# HM_SHT21.net
KiCad netlist of a schematic drawn in EAGLE
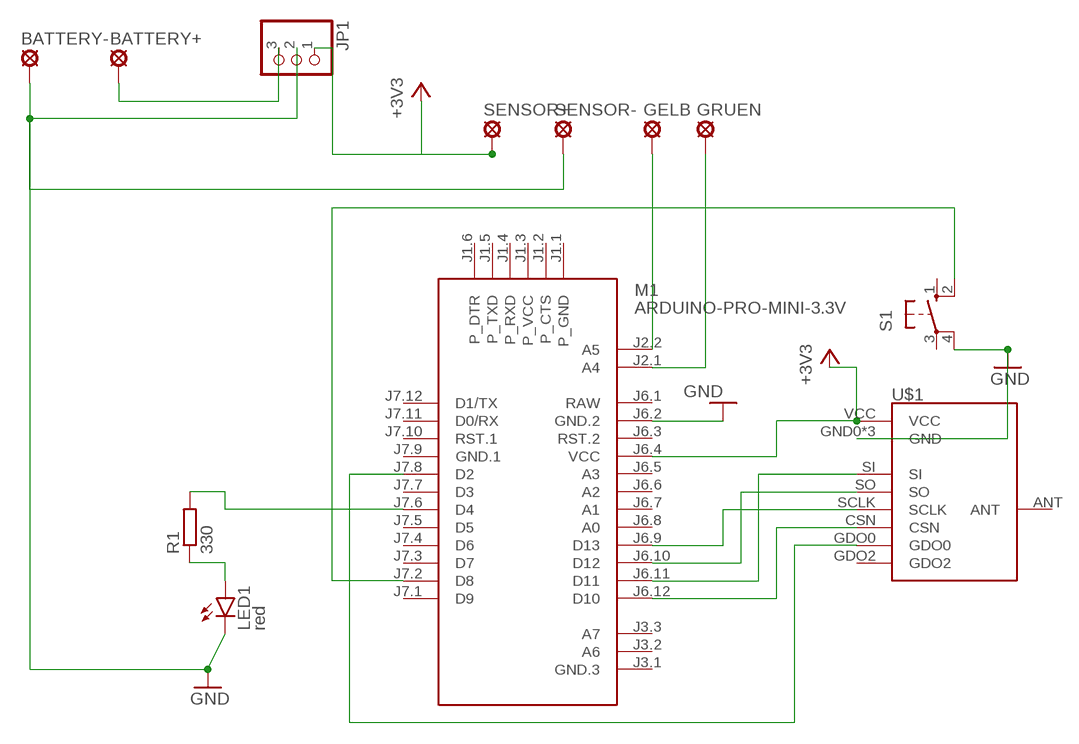
[diagram p0: schematic, sheet 1]

(export (version "E")
  (design (tool "Eeschema 10.0.6"))
  (components
    (comp (ref "BATTERY+")
      (value "LSP11")
      (footprint "eagle-import:LSP11")
      (libsource (lib "eagle-import") (part "LSP11"))
    )
    (comp (ref "BATTERY-")
      (value "LSP11")
      (footprint "eagle-import:LSP11")
      (libsource (lib "eagle-import") (part "LSP11"))
    )
    (comp (ref "GELB")
      (value "LSP11")
      (footprint "eagle-import:LSP11")
      (libsource (lib "eagle-import") (part "LSP11"))
    )
    (comp (ref "GRUEN")
      (value "LSP11")
      (footprint "eagle-import:LSP11")
      (libsource (lib "eagle-import") (part "LSP11"))
    )
    (comp (ref "JP1")
      (value "PINHD-1X3")
      (footprint "eagle-import:1X03")
      (libsource (lib "eagle-import") (part "PINHD-1X3"))
    )
    (comp (ref "LED1")
      (value "red")
      (footprint "eagle-import:LED5MM")
      (libsource (lib "eagle-import") (part "LED5MM"))
    )
    (comp (ref "M1")
      (value "ARDUINO-PRO-MINI-3.3V")
      (footprint "eagle-import:ARDUINO-PRO-MINI")
      (libsource (lib "eagle-import") (part "ARDUINO-PRO-MINI-3.3V"))
    )
    (comp (ref "R1")
      (value "330")
      (footprint "eagle-import:0204_7")
      (libsource (lib "eagle-import") (part "R-EU_0204/7"))
    )
    (comp (ref "S1")
      (value "10-XX")
      (footprint "eagle-import:B3F-10XX")
      (fields (field (name "MPN") "B3F-1000"))
      (libsource (lib "eagle-import") (part "10-XX"))
    )
    (comp (ref "SENSOR+")
      (value "LSP11")
      (footprint "eagle-import:LSP11")
      (libsource (lib "eagle-import") (part "LSP11"))
    )
    (comp (ref "SENSOR-")
      (value "LSP11")
      (footprint "eagle-import:LSP11")
      (libsource (lib "eagle-import") (part "LSP11"))
    )
    (comp (ref "U$1")
      (value "CC1101")
      (footprint "eagle-import:CC1101")
      (libsource (lib "eagle-import") (part "CC1101"))
    )
  )
  (nets
    (net (code "1") (name "+3V3") (class "Default")
      (node (ref "JP1") (pin "1") (pinfunction "1_1") (pintype "passive"))
      (node (ref "M1") (pin "J6.4") (pinfunction "VCC_J6.4") (pintype "power_in"))
      (node (ref "SENSOR+") (pin "MP") (pinfunction "MP_MP") (pintype "passive"))
      (node (ref "U$1") (pin "VCC") (pinfunction "VCC_VCC") (pintype "power_in"))
    )
    (net (code "2") (name "/GND.1") (class "Default")
      (node (ref "M1") (pin "J7.9") (pinfunction "GND.1_J7.9") (pintype "power_in"))
    )
    (net (code "3") (name "/RAW") (class "Default")
      (node (ref "M1") (pin "J6.1") (pinfunction "RAW_J6.1") (pintype "power_in"))
    )
    (net (code "4") (name "GND") (class "Default")
      (node (ref "BATTERY-") (pin "MP") (pinfunction "MP_MP") (pintype "passive"))
      (node (ref "JP1") (pin "2") (pinfunction "2_2") (pintype "passive"))
      (node (ref "LED1") (pin "K") (pinfunction "C_K") (pintype "passive"))
      (node (ref "M1") (pin "J6.2") (pinfunction "GND.2_J6.2") (pintype "power_in"))
      (node (ref "S1") (pin "4") (pinfunction "P1_4") (pintype "passive"))
      (node (ref "SENSOR-") (pin "MP") (pinfunction "MP_MP") (pintype "passive"))
      (node (ref "U$1") (pin "GND0") (pinfunction "GND_GND0") (pintype "power_in"))
      (node (ref "U$1") (pin "GND1") (pinfunction "GND_GND1") (pintype "power_in"))
      (node (ref "U$1") (pin "GND2") (pinfunction "GND_GND2") (pintype "power_in"))
    )
    (net (code "5") (name "Net-(BATTERY+-PadMP)") (class "Default")
      (node (ref "BATTERY+") (pin "MP") (pinfunction "MP_MP") (pintype "passive"))
      (node (ref "JP1") (pin "3") (pinfunction "3_3") (pintype "passive"))
    )
    (net (code "6") (name "Net-(LED1-PadA)") (class "Default")
      (node (ref "LED1") (pin "A") (pinfunction "A_A") (pintype "passive"))
      (node (ref "R1") (pin "1") (pinfunction "1_1") (pintype "passive"))
    )
    (net (code "7") (name "Net-(M1-A4)") (class "Default")
      (node (ref "GRUEN") (pin "MP") (pinfunction "MP_MP") (pintype "passive"))
      (node (ref "M1") (pin "J2.1") (pinfunction "A4_J2.1") (pintype "bidirectional"))
    )
    (net (code "8") (name "Net-(M1-A5)") (class "Default")
      (node (ref "GELB") (pin "MP") (pinfunction "MP_MP") (pintype "passive"))
      (node (ref "M1") (pin "J2.2") (pinfunction "A5_J2.2") (pintype "bidirectional"))
    )
    (net (code "9") (name "Net-(M1-D2)") (class "Default")
      (node (ref "M1") (pin "J7.8") (pinfunction "D2_J7.8") (pintype "bidirectional"))
      (node (ref "U$1") (pin "GDO0") (pinfunction "GDO0_GDO0") (pintype "output"))
    )
    (net (code "10") (name "Net-(M1-D4)") (class "Default")
      (node (ref "M1") (pin "J7.6") (pinfunction "D4_J7.6") (pintype "bidirectional"))
      (node (ref "R1") (pin "2") (pinfunction "2_2") (pintype "passive"))
    )
    (net (code "11") (name "Net-(M1-D8)") (class "Default")
      (node (ref "M1") (pin "J7.2") (pinfunction "D8_J7.2") (pintype "bidirectional"))
      (node (ref "S1") (pin "2") (pinfunction "S1_2") (pintype "passive"))
    )
    (net (code "12") (name "Net-(M1-D10)") (class "Default")
      (node (ref "M1") (pin "J6.12") (pinfunction "D10_J6.12") (pintype "bidirectional"))
      (node (ref "U$1") (pin "CSN") (pinfunction "CSN_CSN") (pintype "bidirectional"))
    )
    (net (code "13") (name "Net-(M1-D11)") (class "Default")
      (node (ref "M1") (pin "J6.11") (pinfunction "D11_J6.11") (pintype "bidirectional"))
      (node (ref "U$1") (pin "SI") (pinfunction "SI_SI") (pintype "input"))
    )
    (net (code "14") (name "Net-(M1-D12)") (class "Default")
      (node (ref "M1") (pin "J6.10") (pinfunction "D12_J6.10") (pintype "bidirectional"))
      (node (ref "U$1") (pin "SO") (pinfunction "SO_SO") (pintype "output"))
    )
    (net (code "15") (name "Net-(M1-D13)") (class "Default")
      (node (ref "M1") (pin "J6.9") (pinfunction "D13_J6.9") (pintype "bidirectional"))
      (node (ref "U$1") (pin "SCLK") (pinfunction "SCLK_SCLK") (pintype "input"))
    )
    (net (code "16") (name "unconnected-(M1-A0-PadJ6.8)") (class "Default")
      (node (ref "M1") (pin "J6.8") (pinfunction "A0_J6.8") (pintype "bidirectional"))
    )
    (net (code "17") (name "unconnected-(M1-A1-PadJ6.7)") (class "Default")
      (node (ref "M1") (pin "J6.7") (pinfunction "A1_J6.7") (pintype "bidirectional"))
    )
    (net (code "18") (name "unconnected-(M1-A2-PadJ6.6)") (class "Default")
      (node (ref "M1") (pin "J6.6") (pinfunction "A2_J6.6") (pintype "bidirectional"))
    )
    (net (code "19") (name "unconnected-(M1-A3-PadJ6.5)") (class "Default")
      (node (ref "M1") (pin "J6.5") (pinfunction "A3_J6.5") (pintype "bidirectional"))
    )
    (net (code "20") (name "unconnected-(M1-A6-PadJ3.2)") (class "Default")
      (node (ref "M1") (pin "J3.2") (pinfunction "A6_J3.2") (pintype "bidirectional"))
    )
    (net (code "21") (name "unconnected-(M1-A7-PadJ3.3)") (class "Default")
      (node (ref "M1") (pin "J3.3") (pinfunction "A7_J3.3") (pintype "bidirectional"))
    )
    (net (code "22") (name "unconnected-(M1-D0{slash}RX-PadJ7.11)") (class "Default")
      (node (ref "M1") (pin "J7.11") (pinfunction "D0/RX_J7.11") (pintype "bidirectional"))
    )
    (net (code "23") (name "unconnected-(M1-D1{slash}TX-PadJ7.12)") (class "Default")
      (node (ref "M1") (pin "J7.12") (pinfunction "D1/TX_J7.12") (pintype "bidirectional"))
    )
    (net (code "24") (name "unconnected-(M1-D3-PadJ7.7)") (class "Default")
      (node (ref "M1") (pin "J7.7") (pinfunction "D3_J7.7") (pintype "bidirectional"))
    )
    (net (code "25") (name "unconnected-(M1-D5-PadJ7.5)") (class "Default")
      (node (ref "M1") (pin "J7.5") (pinfunction "D5_J7.5") (pintype "bidirectional"))
    )
    (net (code "26") (name "unconnected-(M1-D6-PadJ7.4)") (class "Default")
      (node (ref "M1") (pin "J7.4") (pinfunction "D6_J7.4") (pintype "bidirectional"))
    )
    (net (code "27") (name "unconnected-(M1-D7-PadJ7.3)") (class "Default")
      (node (ref "M1") (pin "J7.3") (pinfunction "D7_J7.3") (pintype "bidirectional"))
    )
    (net (code "28") (name "unconnected-(M1-D9-PadJ7.1)") (class "Default")
      (node (ref "M1") (pin "J7.1") (pinfunction "D9_J7.1") (pintype "bidirectional"))
    )
    (net (code "29") (name "unconnected-(M1-GND.3-PadJ3.1)") (class "Default")
      (node (ref "M1") (pin "J3.1") (pinfunction "GND.3_J3.1") (pintype "bidirectional"))
    )
    (net (code "30") (name "unconnected-(M1-P_CTS-PadJ1.2)") (class "Default")
      (node (ref "M1") (pin "J1.2") (pinfunction "P_CTS_J1.2") (pintype "bidirectional"))
    )
    (net (code "31") (name "unconnected-(M1-P_DTR-PadJ1.6)") (class "Default")
      (node (ref "M1") (pin "J1.6") (pinfunction "P_DTR_J1.6") (pintype "bidirectional"))
    )
    (net (code "32") (name "unconnected-(M1-P_GND-PadJ1.1)") (class "Default")
      (node (ref "M1") (pin "J1.1") (pinfunction "P_GND_J1.1") (pintype "bidirectional"))
    )
    (net (code "33") (name "unconnected-(M1-P_RXD-PadJ1.4)") (class "Default")
      (node (ref "M1") (pin "J1.4") (pinfunction "P_RXD_J1.4") (pintype "bidirectional"))
    )
    (net (code "34") (name "unconnected-(M1-P_TXD-PadJ1.5)") (class "Default")
      (node (ref "M1") (pin "J1.5") (pinfunction "P_TXD_J1.5") (pintype "bidirectional"))
    )
    (net (code "35") (name "unconnected-(M1-P_VCC-PadJ1.3)") (class "Default")
      (node (ref "M1") (pin "J1.3") (pinfunction "P_VCC_J1.3") (pintype "bidirectional"))
    )
    (net (code "36") (name "unconnected-(M1-RST.1-PadJ7.10)") (class "Default")
      (node (ref "M1") (pin "J7.10") (pinfunction "RST.1_J7.10") (pintype "bidirectional"))
    )
    (net (code "37") (name "unconnected-(M1-RST.2-PadJ6.3)") (class "Default")
      (node (ref "M1") (pin "J6.3") (pinfunction "RST.2_J6.3") (pintype "bidirectional"))
    )
    (net (code "38") (name "unconnected-(S1-P-Pad3)") (class "Default")
      (node (ref "S1") (pin "3") (pinfunction "P_3") (pintype "passive"))
    )
    (net (code "39") (name "unconnected-(S1-S-Pad1)") (class "Default")
      (node (ref "S1") (pin "1") (pinfunction "S_1") (pintype "passive"))
    )
    (net (code "40") (name "unconnected-(U$1-PadANT)") (class "Default")
      (node (ref "U$1") (pin "ANT") (pinfunction "ANT_ANT") (pintype "input"))
    )
    (net (code "41") (name "unconnected-(U$1-PadGDO2)") (class "Default")
      (node (ref "U$1") (pin "GDO2") (pinfunction "GDO2_GDO2") (pintype "output"))
    )
  )
)
